# 02_USB_MCU.net
KiCad netlist of a schematic drawn in Altium Designer
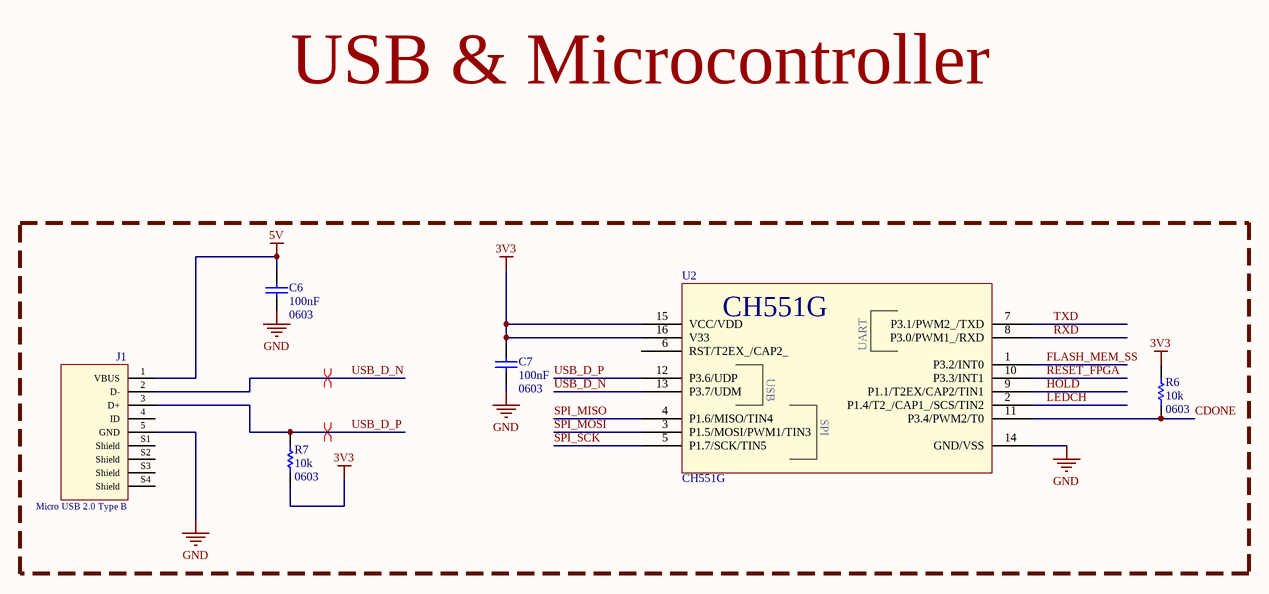
[diagram p0: 02_USB_MCU.SchDoc]

(export (version "E")
  (design (tool "Eeschema 10.0.6"))
  (components
    (comp (ref "C6")
      (value "100nF")
      (footprint "0603 CAP")
      (description "Capacitor")
      (fields (field (name "PACKAGE") "0603") (field (name "Comment") "Ceramic capacitor"))
      (libsource (lib "NodeFPGA") (part "Capacitor"))
    )
    (comp (ref "C7")
      (value "100nF")
      (footprint "0603 CAP")
      (description "Capacitor")
      (fields (field (name "PACKAGE") "0603") (field (name "Comment") "Ceramic capacitor"))
      (libsource (lib "NodeFPGA") (part "Capacitor"))
    )
    (comp (ref "J1")
      (value "Micro USB 2.0 Type B")
      (footprint "629105136821")
      (description "Micro USB 2.0 Type B Horizontal SMT 5 Contacts WR-COM")
      (fields (field (name "PART NUMBER") "629105136821") (field (name "PUBLISHER") "Wurth Elektronik"))
      (libsource (lib "GSATFPGA") (part "629105136821"))
    )
    (comp (ref "R6")
      (value "10k")
      (footprint "Resistencia 0603")
      (description "Resistor")
      (fields (field (name "PACKAGE") "0603"))
      (libsource (lib "NodeFPGA") (part "Resistor"))
    )
    (comp (ref "R7")
      (value "10k")
      (footprint "Resistencia 0603")
      (description "Resistor")
      (fields (field (name "PACKAGE") "0603"))
      (libsource (lib "NodeFPGA") (part "Resistor"))
    )
    (comp (ref "U2")
      (value "CH551G")
      (footprint "CH551")
      (description "Microcontroller wUSB support")
      (libsource (lib "GSATFPGA") (part "CH551G"))
    )
  )
  (nets
    (net (code "1") (name "/CDONE") (class "Default")
      (node (ref "R6") (pin "1") (pinfunction "1_1") (pintype "passive"))
      (node (ref "U2") (pin "11") (pinfunction "P3.4/PWM2/T0_11") (pintype "passive"))
    )
    (net (code "2") (name "/FLASH_MEM_SS") (class "Default")
      (node (ref "U2") (pin "1") (pinfunction "P3.2/INT0_1") (pintype "passive"))
    )
    (net (code "3") (name "/HOLD") (class "Default")
      (node (ref "U2") (pin "9") (pinfunction "P1.1/T2EX/CAP2/TIN1_9") (pintype "passive"))
    )
    (net (code "4") (name "/LEDCH") (class "Default")
      (node (ref "U2") (pin "2") (pinfunction "P1.4/T2_/CAP1_/SCS/TIN2_2") (pintype "passive"))
    )
    (net (code "5") (name "/RESET_FPGA") (class "Default")
      (node (ref "U2") (pin "10") (pinfunction "P3.3/INT1_10") (pintype "passive"))
    )
    (net (code "6") (name "/RXD") (class "Default")
      (node (ref "U2") (pin "8") (pinfunction "P3.0/PWM1_/RXD_8") (pintype "passive"))
    )
    (net (code "7") (name "/SPI_MISO") (class "Default")
      (node (ref "U2") (pin "4") (pinfunction "P1.6/MISO/TIN4_4") (pintype "passive"))
    )
    (net (code "8") (name "/SPI_MOSI") (class "Default")
      (node (ref "U2") (pin "3") (pinfunction "P1.5/MOSI/PWM1/TIN3_3") (pintype "passive"))
    )
    (net (code "9") (name "/SPI_SCK") (class "Default")
      (node (ref "U2") (pin "5") (pinfunction "P1.7/SCK/TIN5_5") (pintype "passive"))
    )
    (net (code "10") (name "/TXD") (class "Default")
      (node (ref "U2") (pin "7") (pinfunction "P3.1/PWM2_/TXD_7") (pintype "passive"))
    )
    (net (code "11") (name "/USB_D_N") (class "Default")
      (node (ref "J1") (pin "2") (pinfunction "D-_2") (pintype "passive"))
      (node (ref "U2") (pin "13") (pinfunction "P3.7/UDM_13") (pintype "passive"))
    )
    (net (code "12") (name "/USB_D_P") (class "Default")
      (node (ref "J1") (pin "3") (pinfunction "D+_3") (pintype "passive"))
      (node (ref "R7") (pin "1") (pinfunction "1_1") (pintype "passive"))
      (node (ref "U2") (pin "12") (pinfunction "P3.6/UDP_12") (pintype "passive"))
    )
    (net (code "13") (name "3V3") (class "Default")
      (node (ref "C7") (pin "1") (pinfunction "1_1") (pintype "passive"))
      (node (ref "R6") (pin "2") (pinfunction "2_2") (pintype "passive"))
      (node (ref "R7") (pin "2") (pinfunction "2_2") (pintype "passive"))
      (node (ref "U2") (pin "15") (pinfunction "VCC/VDD_15") (pintype "passive"))
      (node (ref "U2") (pin "16") (pinfunction "V33_16") (pintype "passive"))
    )
    (net (code "14") (name "5V") (class "Default")
      (node (ref "C6") (pin "1") (pinfunction "1_1") (pintype "passive"))
      (node (ref "J1") (pin "1") (pinfunction "VBUS_1") (pintype "passive"))
    )
    (net (code "15") (name "GND") (class "Default")
      (node (ref "C6") (pin "2") (pinfunction "2_2") (pintype "passive"))
      (node (ref "C7") (pin "2") (pinfunction "2_2") (pintype "passive"))
      (node (ref "J1") (pin "5") (pinfunction "GND_5") (pintype "passive"))
      (node (ref "U2") (pin "14") (pinfunction "GND/VSS_14") (pintype "passive"))
    )
    (net (code "16") (name "unconnected-(J1-ID-Pad4)") (class "Default")
      (node (ref "J1") (pin "4") (pinfunction "ID_4") (pintype "passive"))
    )
    (net (code "17") (name "unconnected-(J1-Shield-PadS1)") (class "Default")
      (node (ref "J1") (pin "S1") (pinfunction "Shield_S1") (pintype "passive"))
    )
    (net (code "18") (name "unconnected-(J1-Shield-PadS2)") (class "Default")
      (node (ref "J1") (pin "S2") (pinfunction "Shield_S2") (pintype "passive"))
    )
    (net (code "19") (name "unconnected-(J1-Shield-PadS3)") (class "Default")
      (node (ref "J1") (pin "S3") (pinfunction "Shield_S3") (pintype "passive"))
    )
    (net (code "20") (name "unconnected-(J1-Shield-PadS4)") (class "Default")
      (node (ref "J1") (pin "S4") (pinfunction "Shield_S4") (pintype "passive"))
    )
    (net (code "21") (name "unconnected-(U2-RST{slash}T2EX_{slash}CAP2_-Pad6)") (class "Default")
      (node (ref "U2") (pin "6") (pinfunction "RST/T2EX_/CAP2__6") (pintype "passive"))
    )
  )
)
